# POGOTEST-MK2RP2040.net
KiCad netlist of a schematic drawn in EAGLE
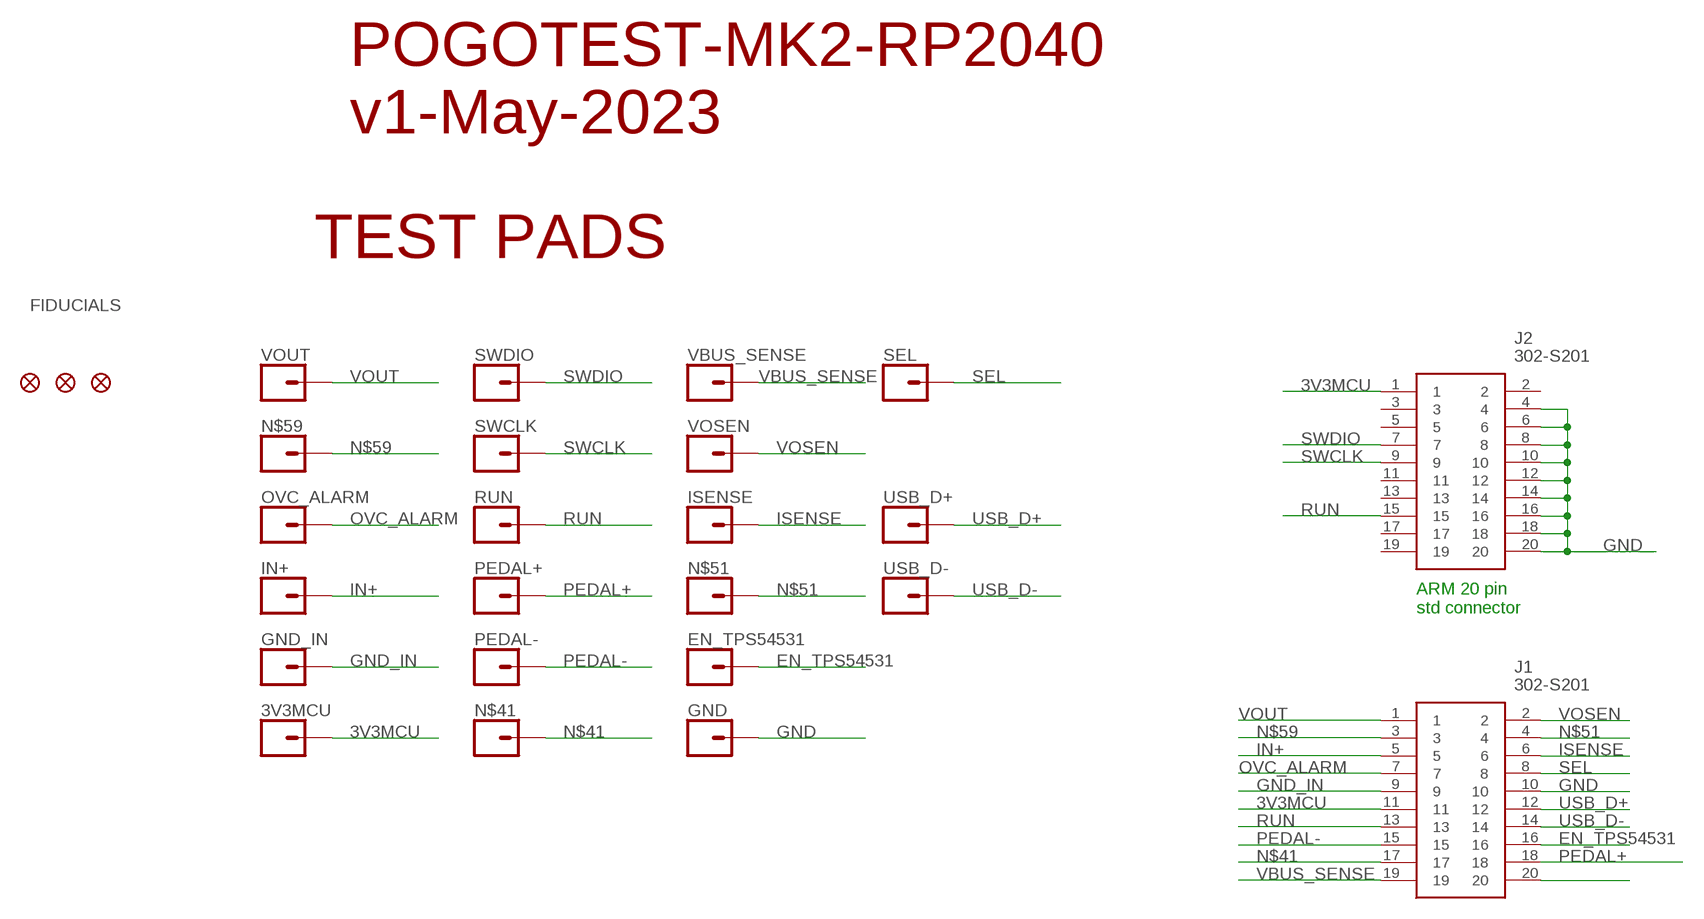
[diagram p0: schematic, sheet 1]

(export (version "E")
  (design (tool "Eeschema 10.0.6"))
  (components
    (comp (ref "3V3MCU")
      (value "CONN_01POGOPIN_HOLE_LARGE")
      (footprint "eagle-import:1X01_POGOPIN_HOLE_0.061_DIA")
      (libsource (lib "eagle-import") (part "CONN_01POGOPIN_HOLE_LARGE"))
    )
    (comp (ref "EN_TPS54531")
      (value "CONN_01POGOPIN_HOLE_LARGE")
      (footprint "eagle-import:1X01_POGOPIN_HOLE_0.061_DIA")
      (libsource (lib "eagle-import") (part "CONN_01POGOPIN_HOLE_LARGE"))
    )
    (comp (ref "FID3")
      (value "FIDUCIAL1X2")
      (footprint "eagle-import:FIDUCIAL-1X2")
      (libsource (lib "eagle-import") (part "FIDUCIAL1X2"))
    )
    (comp (ref "FID5")
      (value "FIDUCIAL1X2")
      (footprint "eagle-import:FIDUCIAL-1X2")
      (libsource (lib "eagle-import") (part "FIDUCIAL1X2"))
    )
    (comp (ref "FID6")
      (value "FIDUCIAL1X2")
      (footprint "eagle-import:FIDUCIAL-1X2")
      (libsource (lib "eagle-import") (part "FIDUCIAL1X2"))
    )
    (comp (ref "GND")
      (value "CONN_01POGOPIN_HOLE_LARGE")
      (footprint "eagle-import:1X01_POGOPIN_HOLE_0.061_DIA")
      (libsource (lib "eagle-import") (part "CONN_01POGOPIN_HOLE_LARGE"))
    )
    (comp (ref "GND_IN")
      (value "CONN_01POGOPIN_HOLE_LARGE")
      (footprint "eagle-import:1X01_POGOPIN_HOLE_0.061_DIA")
      (libsource (lib "eagle-import") (part "CONN_01POGOPIN_HOLE_LARGE"))
    )
    (comp (ref "IN+")
      (value "CONN_01POGOPIN_HOLE_LARGE")
      (footprint "eagle-import:1X01_POGOPIN_HOLE_0.061_DIA")
      (libsource (lib "eagle-import") (part "CONN_01POGOPIN_HOLE_LARGE"))
    )
    (comp (ref "ISENSE")
      (value "CONN_01POGOPIN_HOLE_LARGE")
      (footprint "eagle-import:1X01_POGOPIN_HOLE_0.061_DIA")
      (libsource (lib "eagle-import") (part "CONN_01POGOPIN_HOLE_LARGE"))
    )
    (comp (ref "J1")
      (value "302-S201")
      (footprint "eagle-import:SHDR20W66P254_2X10_3300X905X90")
      (libsource (lib "eagle-import") (part "302-S201"))
    )
    (comp (ref "J2")
      (value "302-S201")
      (footprint "eagle-import:SHDR20W66P254_2X10_3300X905X90")
      (libsource (lib "eagle-import") (part "302-S201"))
    )
    (comp (ref "N$41")
      (value "CONN_01POGOPIN_HOLE_LARGE")
      (footprint "eagle-import:1X01_POGOPIN_HOLE_0.061_DIA")
      (libsource (lib "eagle-import") (part "CONN_01POGOPIN_HOLE_LARGE"))
    )
    (comp (ref "N$51")
      (value "CONN_01POGOPIN_HOLE_LARGE")
      (footprint "eagle-import:1X01_POGOPIN_HOLE_0.061_DIA")
      (libsource (lib "eagle-import") (part "CONN_01POGOPIN_HOLE_LARGE"))
    )
    (comp (ref "N$59")
      (value "CONN_01POGOPIN_HOLE_LARGE")
      (footprint "eagle-import:1X01_POGOPIN_HOLE_0.061_DIA")
      (libsource (lib "eagle-import") (part "CONN_01POGOPIN_HOLE_LARGE"))
    )
    (comp (ref "OVC_ALARM")
      (value "CONN_01POGOPIN_HOLE_LARGE")
      (footprint "eagle-import:1X01_POGOPIN_HOLE_0.061_DIA")
      (libsource (lib "eagle-import") (part "CONN_01POGOPIN_HOLE_LARGE"))
    )
    (comp (ref "PEDAL+")
      (value "CONN_01POGOPIN_HOLE_LARGE")
      (footprint "eagle-import:1X01_POGOPIN_HOLE_0.061_DIA")
      (libsource (lib "eagle-import") (part "CONN_01POGOPIN_HOLE_LARGE"))
    )
    (comp (ref "PEDAL-")
      (value "CONN_01POGOPIN_HOLE_LARGE")
      (footprint "eagle-import:1X01_POGOPIN_HOLE_0.061_DIA")
      (libsource (lib "eagle-import") (part "CONN_01POGOPIN_HOLE_LARGE"))
    )
    (comp (ref "RUN")
      (value "CONN_01POGOPIN_HOLE_LARGE")
      (footprint "eagle-import:1X01_POGOPIN_HOLE_0.061_DIA")
      (libsource (lib "eagle-import") (part "CONN_01POGOPIN_HOLE_LARGE"))
    )
    (comp (ref "SEL")
      (value "CONN_01POGOPIN_HOLE_LARGE")
      (footprint "eagle-import:1X01_POGOPIN_HOLE_0.061_DIA")
      (libsource (lib "eagle-import") (part "CONN_01POGOPIN_HOLE_LARGE"))
    )
    (comp (ref "SWCLK")
      (value "CONN_01POGOPIN_HOLE_LARGE")
      (footprint "eagle-import:1X01_POGOPIN_HOLE_0.061_DIA")
      (libsource (lib "eagle-import") (part "CONN_01POGOPIN_HOLE_LARGE"))
    )
    (comp (ref "SWDIO")
      (value "CONN_01POGOPIN_HOLE_LARGE")
      (footprint "eagle-import:1X01_POGOPIN_HOLE_0.061_DIA")
      (libsource (lib "eagle-import") (part "CONN_01POGOPIN_HOLE_LARGE"))
    )
    (comp (ref "USB_D+")
      (value "CONN_01POGOPIN_HOLE_LARGE")
      (footprint "eagle-import:1X01_POGOPIN_HOLE_0.061_DIA")
      (libsource (lib "eagle-import") (part "CONN_01POGOPIN_HOLE_LARGE"))
    )
    (comp (ref "USB_D-")
      (value "CONN_01POGOPIN_HOLE_LARGE")
      (footprint "eagle-import:1X01_POGOPIN_HOLE_0.061_DIA")
      (libsource (lib "eagle-import") (part "CONN_01POGOPIN_HOLE_LARGE"))
    )
    (comp (ref "VBUS_SENSE")
      (value "CONN_01POGOPIN_HOLE_LARGE")
      (footprint "eagle-import:1X01_POGOPIN_HOLE_0.061_DIA")
      (libsource (lib "eagle-import") (part "CONN_01POGOPIN_HOLE_LARGE"))
    )
    (comp (ref "VOSEN")
      (value "CONN_01POGOPIN_HOLE_LARGE")
      (footprint "eagle-import:1X01_POGOPIN_HOLE_0.061_DIA")
      (libsource (lib "eagle-import") (part "CONN_01POGOPIN_HOLE_LARGE"))
    )
    (comp (ref "VOUT")
      (value "CONN_01POGOPIN_HOLE_LARGE")
      (footprint "eagle-import:1X01_POGOPIN_HOLE_0.061_DIA")
      (libsource (lib "eagle-import") (part "CONN_01POGOPIN_HOLE_LARGE"))
    )
  )
  (nets
    (net (code "1") (name "/3V3MCU") (class "Default")
      (node (ref "3V3MCU") (pin "2") (pinfunction "1_2") (pintype "passive"))
      (node (ref "J1") (pin "11") (pinfunction "11_11") (pintype "bidirectional"))
      (node (ref "J2") (pin "1") (pinfunction "1_1") (pintype "bidirectional"))
    )
    (net (code "2") (name "/EN_TPS54531") (class "Default")
      (node (ref "EN_TPS54531") (pin "2") (pinfunction "1_2") (pintype "passive"))
      (node (ref "J1") (pin "16") (pinfunction "16_16") (pintype "bidirectional"))
    )
    (net (code "3") (name "/GND") (class "Default")
      (node (ref "GND") (pin "2") (pinfunction "1_2") (pintype "passive"))
      (node (ref "J1") (pin "10") (pinfunction "10_10") (pintype "bidirectional"))
      (node (ref "J2") (pin "10") (pinfunction "10_10") (pintype "bidirectional"))
      (node (ref "J2") (pin "12") (pinfunction "12_12") (pintype "bidirectional"))
      (node (ref "J2") (pin "14") (pinfunction "14_14") (pintype "bidirectional"))
      (node (ref "J2") (pin "16") (pinfunction "16_16") (pintype "bidirectional"))
      (node (ref "J2") (pin "18") (pinfunction "18_18") (pintype "bidirectional"))
      (node (ref "J2") (pin "20") (pinfunction "20_20") (pintype "bidirectional"))
      (node (ref "J2") (pin "4") (pinfunction "4_4") (pintype "bidirectional"))
      (node (ref "J2") (pin "6") (pinfunction "6_6") (pintype "bidirectional"))
      (node (ref "J2") (pin "8") (pinfunction "8_8") (pintype "bidirectional"))
    )
    (net (code "4") (name "/GND_IN") (class "Default")
      (node (ref "GND_IN") (pin "2") (pinfunction "1_2") (pintype "passive"))
      (node (ref "J1") (pin "9") (pinfunction "9_9") (pintype "bidirectional"))
    )
    (net (code "5") (name "/IN+") (class "Default")
      (node (ref "IN+") (pin "2") (pinfunction "1_2") (pintype "passive"))
      (node (ref "J1") (pin "5") (pinfunction "5_5") (pintype "bidirectional"))
    )
    (net (code "6") (name "/ISENSE") (class "Default")
      (node (ref "ISENSE") (pin "2") (pinfunction "1_2") (pintype "passive"))
      (node (ref "J1") (pin "6") (pinfunction "6_6") (pintype "bidirectional"))
    )
    (net (code "7") (name "/N$41") (class "Default")
      (node (ref "J1") (pin "17") (pinfunction "17_17") (pintype "bidirectional"))
      (node (ref "N$41") (pin "2") (pinfunction "1_2") (pintype "passive"))
    )
    (net (code "8") (name "/N$51") (class "Default")
      (node (ref "J1") (pin "4") (pinfunction "4_4") (pintype "bidirectional"))
      (node (ref "N$51") (pin "2") (pinfunction "1_2") (pintype "passive"))
    )
    (net (code "9") (name "/N$59") (class "Default")
      (node (ref "J1") (pin "3") (pinfunction "3_3") (pintype "bidirectional"))
      (node (ref "N$59") (pin "2") (pinfunction "1_2") (pintype "passive"))
    )
    (net (code "10") (name "/OVC_ALARM") (class "Default")
      (node (ref "J1") (pin "7") (pinfunction "7_7") (pintype "bidirectional"))
      (node (ref "OVC_ALARM") (pin "2") (pinfunction "1_2") (pintype "passive"))
    )
    (net (code "11") (name "/PEDAL+") (class "Default")
      (node (ref "J1") (pin "18") (pinfunction "18_18") (pintype "bidirectional"))
      (node (ref "PEDAL+") (pin "2") (pinfunction "1_2") (pintype "passive"))
    )
    (net (code "12") (name "/PEDAL-") (class "Default")
      (node (ref "J1") (pin "15") (pinfunction "15_15") (pintype "bidirectional"))
      (node (ref "PEDAL-") (pin "2") (pinfunction "1_2") (pintype "passive"))
    )
    (net (code "13") (name "/RUN") (class "Default")
      (node (ref "J1") (pin "13") (pinfunction "13_13") (pintype "bidirectional"))
      (node (ref "J2") (pin "15") (pinfunction "15_15") (pintype "bidirectional"))
      (node (ref "RUN") (pin "2") (pinfunction "1_2") (pintype "passive"))
    )
    (net (code "14") (name "/SEL") (class "Default")
      (node (ref "J1") (pin "8") (pinfunction "8_8") (pintype "bidirectional"))
      (node (ref "SEL") (pin "2") (pinfunction "1_2") (pintype "passive"))
    )
    (net (code "15") (name "/SWCLK") (class "Default")
      (node (ref "J2") (pin "9") (pinfunction "9_9") (pintype "bidirectional"))
      (node (ref "SWCLK") (pin "2") (pinfunction "1_2") (pintype "passive"))
    )
    (net (code "16") (name "/SWDIO") (class "Default")
      (node (ref "J2") (pin "7") (pinfunction "7_7") (pintype "bidirectional"))
      (node (ref "SWDIO") (pin "2") (pinfunction "1_2") (pintype "passive"))
    )
    (net (code "17") (name "/USB_D+") (class "Default")
      (node (ref "J1") (pin "12") (pinfunction "12_12") (pintype "bidirectional"))
      (node (ref "USB_D+") (pin "2") (pinfunction "1_2") (pintype "passive"))
    )
    (net (code "18") (name "/USB_D-") (class "Default")
      (node (ref "J1") (pin "14") (pinfunction "14_14") (pintype "bidirectional"))
      (node (ref "USB_D-") (pin "2") (pinfunction "1_2") (pintype "passive"))
    )
    (net (code "19") (name "/VBUS_SENSE") (class "Default")
      (node (ref "J1") (pin "19") (pinfunction "19_19") (pintype "bidirectional"))
      (node (ref "VBUS_SENSE") (pin "2") (pinfunction "1_2") (pintype "passive"))
    )
    (net (code "20") (name "/VOSEN") (class "Default")
      (node (ref "J1") (pin "2") (pinfunction "2_2") (pintype "bidirectional"))
      (node (ref "VOSEN") (pin "2") (pinfunction "1_2") (pintype "passive"))
    )
    (net (code "21") (name "/VOUT") (class "Default")
      (node (ref "J1") (pin "1") (pinfunction "1_1") (pintype "bidirectional"))
      (node (ref "VOUT") (pin "2") (pinfunction "1_2") (pintype "passive"))
    )
    (net (code "22") (name "unconnected-(J1-Pad20)") (class "Default")
      (node (ref "J1") (pin "20") (pinfunction "20_20") (pintype "bidirectional"))
    )
    (net (code "23") (name "unconnected-(J2-Pad2)") (class "Default")
      (node (ref "J2") (pin "2") (pinfunction "2_2") (pintype "bidirectional"))
    )
    (net (code "24") (name "unconnected-(J2-Pad3)") (class "Default")
      (node (ref "J2") (pin "3") (pinfunction "3_3") (pintype "bidirectional"))
    )
    (net (code "25") (name "unconnected-(J2-Pad5)") (class "Default")
      (node (ref "J2") (pin "5") (pinfunction "5_5") (pintype "bidirectional"))
    )
    (net (code "26") (name "unconnected-(J2-Pad11)") (class "Default")
      (node (ref "J2") (pin "11") (pinfunction "11_11") (pintype "bidirectional"))
    )
    (net (code "27") (name "unconnected-(J2-Pad13)") (class "Default")
      (node (ref "J2") (pin "13") (pinfunction "13_13") (pintype "bidirectional"))
    )
    (net (code "28") (name "unconnected-(J2-Pad17)") (class "Default")
      (node (ref "J2") (pin "17") (pinfunction "17_17") (pintype "bidirectional"))
    )
    (net (code "29") (name "unconnected-(J2-Pad19)") (class "Default")
      (node (ref "J2") (pin "19") (pinfunction "19_19") (pintype "bidirectional"))
    )
  )
)
